# TEMPLATE_Circuit.net
KiCad netlist of a schematic drawn in Altium Designer
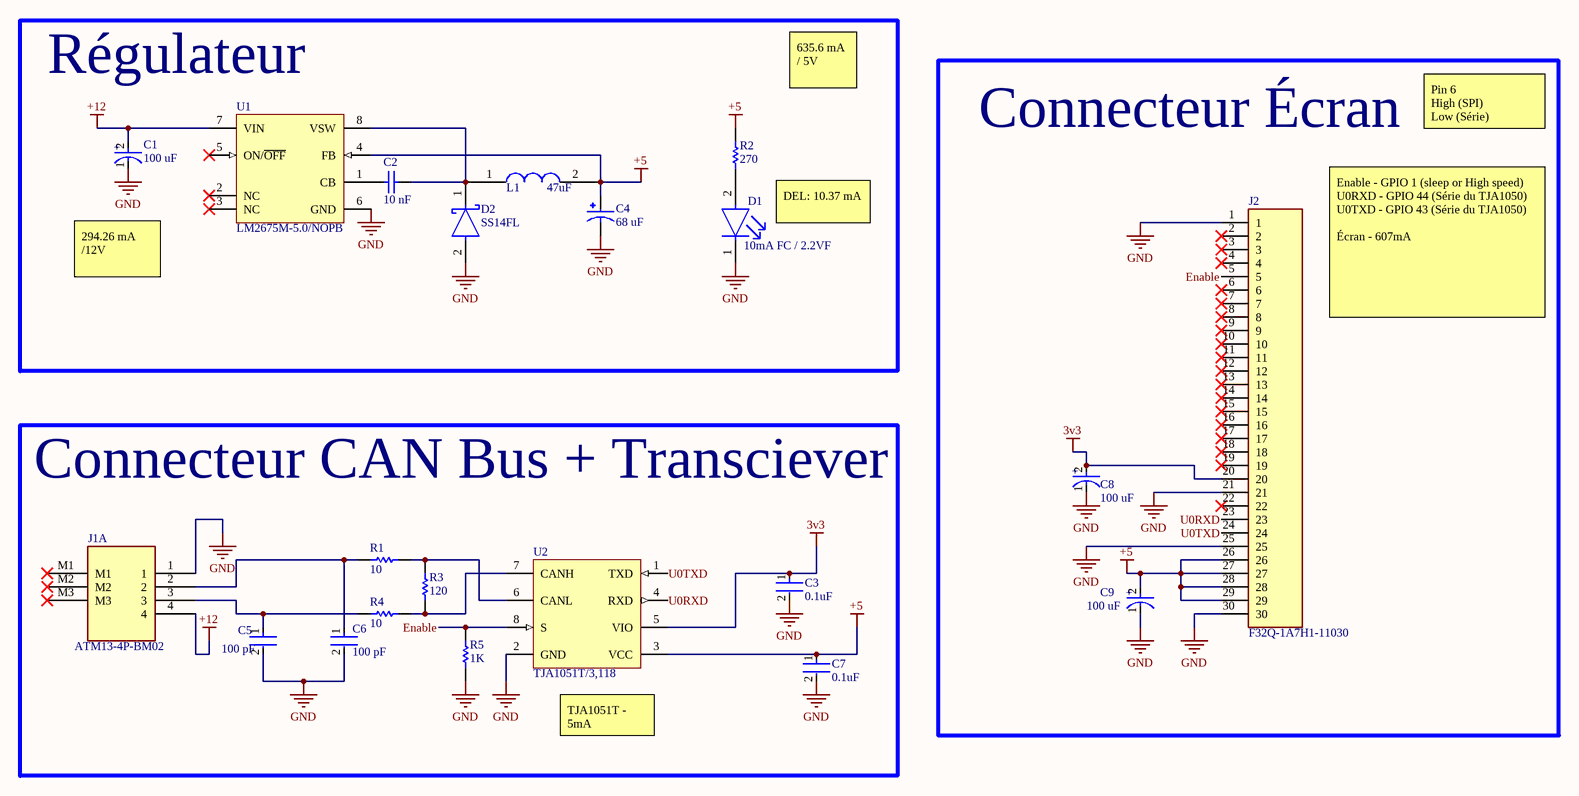
[diagram p0: TEMPLATE_Circuit.SchDoc]

(export (version "E")
  (design (tool "Eeschema 10.0.6"))
  (components
    (comp (ref "C1")
      (value "100 uF")
      (footprint "FP-FKF-MFG")
      (description "CAP ALUM 100UF 20% 50V SMD")
      (fields (field (name "VOLTAGE") "50V") (field (name "TOLERANCE") "20%"))
      (libsource (lib "Altium Content Vault") (part "a00bbbee19879c290e62620ae7e47b1"))
    )
    (comp (ref "C2")
      (value "10 nF")
      (footprint "CAPC1608X90X35ML10T15")
      (description "Chip Capacitor, 10 nF, +/- 10%, 50 V, -55 to 125 degC, 0603 (1608 Metric), RoHS, Tape and Reel")
      (fields (field (name "VOLTAGE") "50V") (field (name "TOLERANCE") "10%"))
      (libsource (lib "Altium Content Vault") (part "CAP-NP-2"))
    )
    (comp (ref "C3")
      (value "0.1uF")
      (footprint "FP-0805-L_2_01_0_2-W_1_25-IPC_B")
      (description "Automotive Ceramic Capacitor, 0805, 100nF, 10%, X7R, 15%, 100V")
      (fields (field (name "TOLERANCE") "10%") (field (name "VOLTAGE") "100V"))
      (libsource (lib "Altium Content Vault") (part "b4654b650e69147ec39a6b967a45e02"))
    )
    (comp (ref "C4")
      (value "68 uF")
      (footprint "CAP_EEEFN1H680XP")
      (fields
        (field (name "MF") "{'manufacturer': u'Panasonic Electronic Components'}")
        (field (name "MP") "EEEFN1H680XP")
      )
      (libsource (lib "EEEFN1H680XP") (part "EEEFN1H680XP"))
    )
    (comp (ref "C5")
      (value "100 pF")
      (footprint "FP-CC0805-0_1-0_7-IPC_A")
      (description "CAP CER 100PF 50V C0G/NPO 0805")
      (fields (field (name "VOLTAGE") "50V") (field (name "TOLERANCE") "5%"))
      (libsource (lib "Altium Content Vault") (part "02cd4be3c70576c341d710602a673aa"))
    )
    (comp (ref "C6")
      (value "100 pF")
      (footprint "FP-CC0805-0_1-0_7-IPC_A")
      (description "CAP CER 100PF 50V C0G/NPO 0805")
      (fields (field (name "VOLTAGE") "50V") (field (name "TOLERANCE") "5%"))
      (libsource (lib "Altium Content Vault") (part "02cd4be3c70576c341d710602a673aa"))
    )
    (comp (ref "C7")
      (value "0.1uF")
      (footprint "FP-0805-L_2_01_0_2-W_1_25-IPC_B")
      (description "Automotive Ceramic Capacitor, 0805, 100nF, 10%, X7R, 15%, 100V")
      (fields (field (name "TOLERANCE") "10%") (field (name "VOLTAGE") "100V"))
      (libsource (lib "Altium Content Vault") (part "b4654b650e69147ec39a6b967a45e02"))
    )
    (comp (ref "C8")
      (value "100 uF")
      (footprint "FP-FKF-MFG")
      (description "CAP ALUM 100UF 20% 50V SMD")
      (fields (field (name "VOLTAGE") "50V") (field (name "TOLERANCE") "20%"))
      (libsource (lib "Altium Content Vault") (part "a00bbbee19879c290e62620ae7e47b1"))
    )
    (comp (ref "C9")
      (value "100 uF")
      (footprint "FP-FKF-MFG")
      (description "CAP ALUM 100UF 20% 50V SMD")
      (fields (field (name "VOLTAGE") "50V") (field (name "TOLERANCE") "20%"))
      (libsource (lib "Altium Content Vault") (part "a00bbbee19879c290e62620ae7e47b1"))
    )
    (comp (ref "D1")
      (value "10mA FC / 2.2VF")
      (footprint "FP-SML-210-MFG")
      (description "LED GREEN CLEAR 0805 SMD")
      (fields (field (name "MANUFACTURER PART NUMBER") "SML-210MTT86") (field (name "MANUFACTURER") "ROHM"))
      (libsource (lib "Altium Content Vault") (part "8706943c75ba83719d021d2fdc84c58"))
    )
    (comp (ref "D2")
      (value "SS14FL")
      (footprint "FP-425AD-MFG")
      (description "DIODE SCHOTTKY 40V 1A SOD123F")
      (fields
        (field (name "MANUFACTURER") "ON Semiconductor")
        (field (name "OCTOPART") "https://octopart.com/ss14fl-on+semiconductor-84331601")
      )
      (libsource (lib "Altium Content Vault") (part "c1678fac7984e62e0809fbf79c06691"))
    )
    (comp (ref "J1")
      (value "ATM13-4P-BM02")
      (footprint "ATM134PBM02")
      (libsource (lib "PCB_MCP_Final") (part "ATM13-4P-BM02"))
    )
    (comp (ref "J2")
      (value "F32Q-1A7H1-11030")
      (footprint "AMPHENOL_F32Q-1A7H1-11030")
      (fields (field (name "MF") "Amphenol ICC / Aorora"))
      (libsource (lib "F32Q-1A7H1-11030") (part "F32Q-1A7H1-11030"))
    )
    (comp (ref "L1")
      (value "47uF")
      (footprint "NPI31W470MTRF")
      (libsource (lib "NPI31W470MTRF") (part "TEMPLATE_Circuit"))
    )
    (comp (ref "R1")
      (value "10")
      (footprint "RESC2013X50X30NL20T20")
      (fields (field (name "MANUFACTURER") "Vishay Dale") (field (name "PART NUMBER") "CRCW080510R0FKEA"))
      (libsource (lib "Altium Content Vault") (part "RES"))
    )
    (comp (ref "R2")
      (value "270")
      (footprint "RESC2013X60X40NL20T25")
      (fields (field (name "MANUFACTURER") "Panasonic") (field (name "PART NUMBER") "ERA6AEB151V"))
      (libsource (lib "Altium Content Vault") (part "RES"))
    )
    (comp (ref "R3")
      (value "120")
      (footprint "RESC2013X60X40ML20T25")
      (fields (field (name "MANUFACTURER") "Panasonic") (field (name "PART NUMBER") "ERA6AEB121V"))
      (libsource (lib "Altium Content Vault") (part "RES"))
    )
    (comp (ref "R4")
      (value "10")
      (footprint "RESC2013X50X30NL20T20")
      (fields (field (name "MANUFACTURER") "Vishay Dale") (field (name "PART NUMBER") "CRCW080510R0FKEA"))
      (libsource (lib "Altium Content Vault") (part "RES"))
    )
    (comp (ref "R5")
      (value "1K")
      (footprint "RESC2013X60X35ML10T20")
      (description "Chip Resistor, 1 KOhm, +/- 1%, 125 mW, -55 to 155 degC, 0805 (2012 Metric), RoHS, Tape and Reel")
      (fields (field (name "TOLERANCE") "1%") (field (name "MANUFACTURER") "Yageo"))
      (libsource (lib "Altium Content Vault") (part "RES-2"))
    )
    (comp (ref "U1")
      (value "LM2675M-5.0/NOPB")
      (footprint "D0008A_L")
      (fields (field (name "MANUFACTURER") "Texas Instruments"))
      (libsource (lib "Altium Content Vault") (part "PM-REG-LM2675M-12"))
    )
    (comp (ref "U2")
      (value "TJA1051T/3,118")
      (footprint "NXP-SOIC-8_L")
      (description "High-Speed CAN Transceiver, 3 to 5 V, 8-Pin SOIC (SOT96-1), RoHS, Tape and Reel")
      (fields (field (name "MANUFACTURER") "NXP"))
      (libsource (lib "Altium Content Vault") (part "NXP-TJA1051T_3-SOIC-8"))
    )
  )
  (nets
    (net (code "1") (name "+5") (class "Default")
      (node (ref "C4") (pin "1") (pinfunction "1_1") (pintype "passive"))
      (node (ref "C7") (pin "1") (pinfunction "1_1") (pintype "passive"))
      (node (ref "C9") (pin "2") (pinfunction "A_2") (pintype "passive"))
      (node (ref "J2") (pin "26") (pinfunction "26_26") (pintype "passive"))
      (node (ref "J2") (pin "27") (pinfunction "27_27") (pintype "passive"))
      (node (ref "J2") (pin "28") (pinfunction "28_28") (pintype "passive"))
      (node (ref "J2") (pin "29") (pinfunction "29_29") (pintype "passive"))
      (node (ref "L1") (pin "2") (pinfunction "2_2") (pintype "passive"))
      (node (ref "R2") (pin "2") (pinfunction "2_2") (pintype "passive"))
      (node (ref "U1") (pin "4") (pinfunction "FB_4") (pintype "input"))
      (node (ref "U2") (pin "3") (pinfunction "VCC_3") (pintype "power_in"))
    )
    (net (code "2") (name "+12") (class "Default")
      (node (ref "C1") (pin "2") (pinfunction "A_2") (pintype "passive"))
      (node (ref "J1") (pin "4") (pinfunction "4_4") (pintype "passive"))
      (node (ref "U1") (pin "7") (pinfunction "VIN_7") (pintype "power_in"))
    )
    (net (code "3") (name "/Enable") (class "Default")
      (node (ref "J2") (pin "5") (pinfunction "5_5") (pintype "passive"))
      (node (ref "R5") (pin "2") (pinfunction "2_2") (pintype "passive"))
      (node (ref "U2") (pin "8") (pinfunction "S_8") (pintype "input"))
    )
    (net (code "4") (name "/U0RXD") (class "Default")
      (node (ref "J2") (pin "23") (pinfunction "23_23") (pintype "passive"))
      (node (ref "U2") (pin "4") (pinfunction "RXD_4") (pintype "output"))
    )
    (net (code "5") (name "/U0TXD") (class "Default")
      (node (ref "J2") (pin "24") (pinfunction "24_24") (pintype "passive"))
      (node (ref "U2") (pin "1") (pinfunction "TXD_1") (pintype "input"))
    )
    (net (code "6") (name "3v3") (class "Default")
      (node (ref "C3") (pin "1") (pinfunction "1_1") (pintype "passive"))
      (node (ref "C8") (pin "2") (pinfunction "A_2") (pintype "passive"))
      (node (ref "J2") (pin "20") (pinfunction "20_20") (pintype "passive"))
      (node (ref "U2") (pin "5") (pinfunction "VIO_5") (pintype "power_in"))
    )
    (net (code "7") (name "GND") (class "Default")
      (node (ref "C1") (pin "1") (pinfunction "C_1") (pintype "passive"))
      (node (ref "C3") (pin "2") (pinfunction "2_2") (pintype "passive"))
      (node (ref "C4") (pin "2") (pinfunction "2_2") (pintype "passive"))
      (node (ref "C5") (pin "2") (pinfunction "2_2") (pintype "passive"))
      (node (ref "C6") (pin "2") (pinfunction "2_2") (pintype "passive"))
      (node (ref "C7") (pin "2") (pinfunction "2_2") (pintype "passive"))
      (node (ref "C8") (pin "1") (pinfunction "C_1") (pintype "passive"))
      (node (ref "C9") (pin "1") (pinfunction "C_1") (pintype "passive"))
      (node (ref "D1") (pin "1") (pinfunction "C_1") (pintype "passive"))
      (node (ref "D2") (pin "2") (pinfunction "A_2") (pintype "passive"))
      (node (ref "J1") (pin "1") (pinfunction "1_1") (pintype "passive"))
      (node (ref "J2") (pin "1") (pinfunction "1_1") (pintype "passive"))
      (node (ref "J2") (pin "21") (pinfunction "21_21") (pintype "passive"))
      (node (ref "J2") (pin "25") (pinfunction "25_25") (pintype "passive"))
      (node (ref "J2") (pin "30") (pinfunction "30_30") (pintype "passive"))
      (node (ref "R5") (pin "1") (pinfunction "1_1") (pintype "passive"))
      (node (ref "U1") (pin "6") (pinfunction "GND_6") (pintype "power_in"))
      (node (ref "U2") (pin "2") (pinfunction "GND_2") (pintype "power_in"))
    )
    (net (code "8") (name "Net-(C5-Pad1)") (class "Default")
      (node (ref "C5") (pin "1") (pinfunction "1_1") (pintype "passive"))
      (node (ref "J1") (pin "3") (pinfunction "3_3") (pintype "passive"))
      (node (ref "R4") (pin "1") (pinfunction "1_1") (pintype "passive"))
    )
    (net (code "9") (name "Net-(C6-Pad1)") (class "Default")
      (node (ref "C6") (pin "1") (pinfunction "1_1") (pintype "passive"))
      (node (ref "J1") (pin "2") (pinfunction "2_2") (pintype "passive"))
      (node (ref "R1") (pin "1") (pinfunction "1_1") (pintype "passive"))
    )
    (net (code "10") (name "Net-(D1-A)") (class "Default")
      (node (ref "D1") (pin "2") (pinfunction "A_2") (pintype "passive"))
      (node (ref "R2") (pin "1") (pinfunction "1_1") (pintype "passive"))
    )
    (net (code "11") (name "Net-(D2-C)") (class "Default")
      (node (ref "C2") (pin "2") (pinfunction "2_2") (pintype "passive"))
      (node (ref "D2") (pin "1") (pinfunction "C_1") (pintype "passive"))
      (node (ref "L1") (pin "1") (pinfunction "1_1") (pintype "passive"))
      (node (ref "U1") (pin "8") (pinfunction "VSW_8") (pintype "power_in"))
    )
    (net (code "12") (name "Net-(U1-CB)") (class "Default")
      (node (ref "C2") (pin "1") (pinfunction "1_1") (pintype "passive"))
      (node (ref "U1") (pin "1") (pinfunction "CB_1") (pintype "passive"))
    )
    (net (code "13") (name "Net-(U2-CANH)") (class "Default")
      (node (ref "R3") (pin "1") (pinfunction "1_1") (pintype "passive"))
      (node (ref "R4") (pin "2") (pinfunction "2_2") (pintype "passive"))
      (node (ref "U2") (pin "7") (pinfunction "CANH_7") (pintype "passive"))
    )
    (net (code "14") (name "Net-(U2-CANL)") (class "Default")
      (node (ref "R1") (pin "2") (pinfunction "2_2") (pintype "passive"))
      (node (ref "R3") (pin "2") (pinfunction "2_2") (pintype "passive"))
      (node (ref "U2") (pin "6") (pinfunction "CANL_6") (pintype "passive"))
    )
    (net (code "15") (name "unconnected-(J1-PadM1)") (class "Default")
      (node (ref "J1") (pin "M1") (pinfunction "M1_M1") (pintype "passive+no_connect"))
    )
    (net (code "16") (name "unconnected-(J1-PadM2)") (class "Default")
      (node (ref "J1") (pin "M2") (pinfunction "M2_M2") (pintype "passive+no_connect"))
    )
    (net (code "17") (name "unconnected-(J1-PadM3)") (class "Default")
      (node (ref "J1") (pin "M3") (pinfunction "M3_M3") (pintype "passive+no_connect"))
    )
    (net (code "18") (name "unconnected-(J2-Pad2)") (class "Default")
      (node (ref "J2") (pin "2") (pinfunction "2_2") (pintype "passive+no_connect"))
    )
    (net (code "19") (name "unconnected-(J2-Pad3)") (class "Default")
      (node (ref "J2") (pin "3") (pinfunction "3_3") (pintype "passive+no_connect"))
    )
    (net (code "20") (name "unconnected-(J2-Pad4)") (class "Default")
      (node (ref "J2") (pin "4") (pinfunction "4_4") (pintype "passive+no_connect"))
    )
    (net (code "21") (name "unconnected-(J2-Pad6)") (class "Default")
      (node (ref "J2") (pin "6") (pinfunction "6_6") (pintype "passive+no_connect"))
    )
    (net (code "22") (name "unconnected-(J2-Pad7)") (class "Default")
      (node (ref "J2") (pin "7") (pinfunction "7_7") (pintype "passive+no_connect"))
    )
    (net (code "23") (name "unconnected-(J2-Pad8)") (class "Default")
      (node (ref "J2") (pin "8") (pinfunction "8_8") (pintype "passive+no_connect"))
    )
    (net (code "24") (name "unconnected-(J2-Pad9)") (class "Default")
      (node (ref "J2") (pin "9") (pinfunction "9_9") (pintype "passive+no_connect"))
    )
    (net (code "25") (name "unconnected-(J2-Pad10)") (class "Default")
      (node (ref "J2") (pin "10") (pinfunction "10_10") (pintype "passive+no_connect"))
    )
    (net (code "26") (name "unconnected-(J2-Pad11)") (class "Default")
      (node (ref "J2") (pin "11") (pinfunction "11_11") (pintype "passive+no_connect"))
    )
    (net (code "27") (name "unconnected-(J2-Pad12)") (class "Default")
      (node (ref "J2") (pin "12") (pinfunction "12_12") (pintype "passive+no_connect"))
    )
    (net (code "28") (name "unconnected-(J2-Pad13)") (class "Default")
      (node (ref "J2") (pin "13") (pinfunction "13_13") (pintype "passive+no_connect"))
    )
    (net (code "29") (name "unconnected-(J2-Pad14)") (class "Default")
      (node (ref "J2") (pin "14") (pinfunction "14_14") (pintype "passive+no_connect"))
    )
    (net (code "30") (name "unconnected-(J2-Pad15)") (class "Default")
      (node (ref "J2") (pin "15") (pinfunction "15_15") (pintype "passive+no_connect"))
    )
    (net (code "31") (name "unconnected-(J2-Pad16)") (class "Default")
      (node (ref "J2") (pin "16") (pinfunction "16_16") (pintype "passive+no_connect"))
    )
    (net (code "32") (name "unconnected-(J2-Pad17)") (class "Default")
      (node (ref "J2") (pin "17") (pinfunction "17_17") (pintype "passive+no_connect"))
    )
    (net (code "33") (name "unconnected-(J2-Pad18)") (class "Default")
      (node (ref "J2") (pin "18") (pinfunction "18_18") (pintype "passive+no_connect"))
    )
    (net (code "34") (name "unconnected-(J2-Pad19)") (class "Default")
      (node (ref "J2") (pin "19") (pinfunction "19_19") (pintype "passive+no_connect"))
    )
    (net (code "35") (name "unconnected-(J2-Pad22)") (class "Default")
      (node (ref "J2") (pin "22") (pinfunction "22_22") (pintype "passive+no_connect"))
    )
    (net (code "36") (name "unconnected-(U1-NC-Pad2)") (class "Default")
      (node (ref "U1") (pin "2") (pinfunction "NC_2") (pintype "passive+no_connect"))
    )
    (net (code "37") (name "unconnected-(U1-NC-Pad3)") (class "Default")
      (node (ref "U1") (pin "3") (pinfunction "NC_3") (pintype "passive+no_connect"))
    )
    (net (code "38") (name "unconnected-(U1-ON{slash}~{OFF}-Pad5)") (class "Default")
      (node (ref "U1") (pin "5") (pinfunction "ON/~{OFF}_5") (pintype "input+no_connect"))
    )
  )
)
